# SCH_CH32V003EasyUSBBoard_SCH_2024-02-12.net
KiCad netlist of a schematic drawn in EasyEDA
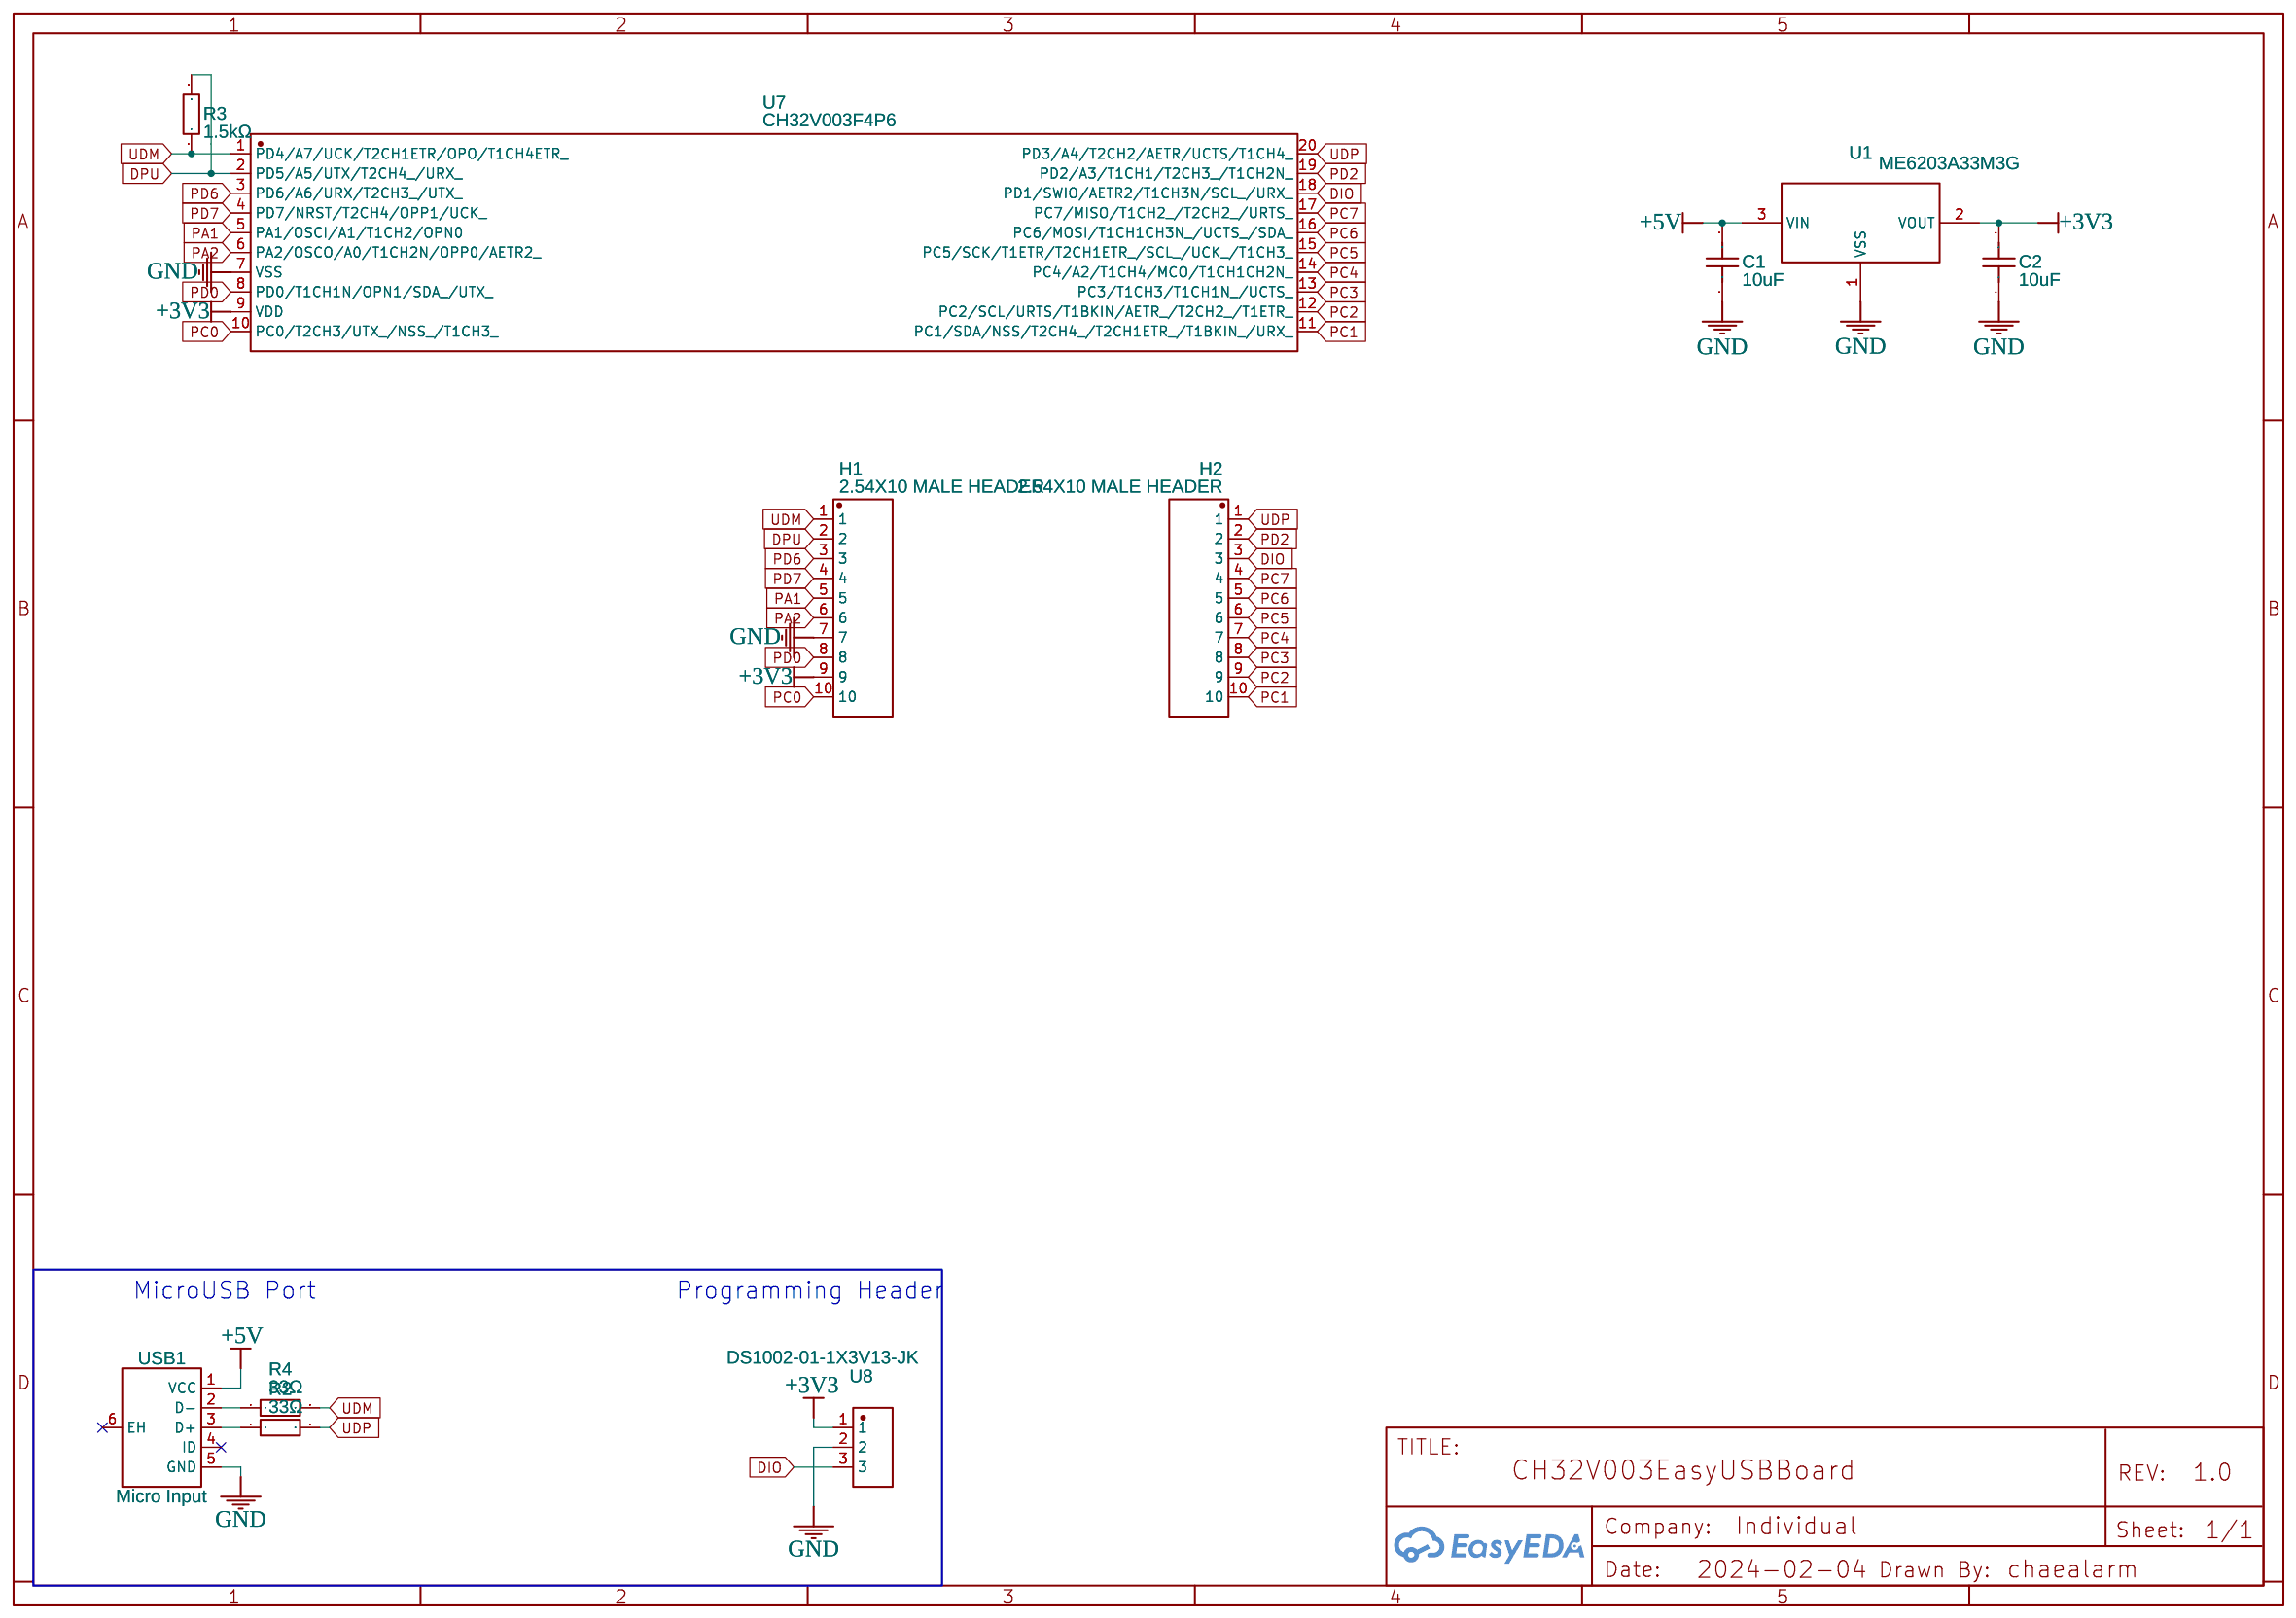
[diagram p0: schematic sheet]

(export (version "E")
  (design (tool "Eeschema 10.0.6"))
  (components
    (comp (ref "C1")
      (value "10uF")
      (fields
        (field (name "Manufacturer Part") "CL10A106KP8NNNC")
        (field (name "Manufacturer") "SAMSUNG(三星)")
      )
      (libsource (lib "") (part "CL10A106KP8NNNC"))
    )
    (comp (ref "C2")
      (value "10uF")
      (fields
        (field (name "Manufacturer Part") "CL10A106KP8NNNC")
        (field (name "Manufacturer") "SAMSUNG(三星)")
      )
      (libsource (lib "") (part "CL10A106KP8NNNC"))
    )
    (comp (ref "H1")
      (value "2.54X10 MALE HEADER")
      (fields
        (field (name "Manufacturer Part") "210S-1*11P L=11.6MMGold-plated black")
        (field (name "Manufacturer") "Ckmtw")
      )
      (libsource (lib "") (part "2.54X10 MALE HEADER"))
    )
    (comp (ref "H2")
      (value "2.54X10 MALE HEADER")
      (fields
        (field (name "Manufacturer Part") "210S-1*11P L=11.6MMGold-plated black")
        (field (name "Manufacturer") "Ckmtw")
      )
      (libsource (lib "") (part "2.54X10 MALE HEADER_1"))
    )
    (comp (ref "R2")
      (value "33Ω")
      (fields
        (field (name "Manufacturer Part") "0603WAF330JT5E")
        (field (name "Manufacturer") "UNI-ROYAL(厚声)")
      )
      (libsource (lib "") (part "0603WAF330JT5E"))
    )
    (comp (ref "R3")
      (value "1.5kΩ")
      (fields
        (field (name "Manufacturer Part") "0603WAF1501T5E")
        (field (name "Manufacturer") "UNI-ROYAL(厚声)")
      )
      (libsource (lib "") (part "0603WAF1501T5E"))
    )
    (comp (ref "R4")
      (value "33Ω")
      (fields
        (field (name "Manufacturer Part") "0603WAF330JT5E")
        (field (name "Manufacturer") "UNI-ROYAL(厚声)")
      )
      (libsource (lib "") (part "0603WAF330JT5E"))
    )
    (comp (ref "U1")
      (value "ME6203A33M3G")
      (fields (field (name "Manufacturer") "MICRONE(南京微盟)"))
      (libsource (lib "") (part "ME6203A33M3G"))
    )
    (comp (ref "U7") (value "CH32V003F4P6") (libsource (lib "") (part "CH32V003F4P6")))
    (comp (ref "U8")
      (value "DS1002-01-1X3V13-JK")
      (fields
        (field (name "Manufacturer Part") "DS1002-01-1x3V13-JK")
        (field (name "Manufacturer") "CONNFLY")
      )
      (libsource (lib "") (part "DS1002-01-1X3V13-JK"))
    )
    (comp (ref "USB1")
      (value "Micro Input")
      (fields
        (field (name "Manufacturer Part") "U254-051T-4BH23-S2B")
        (field (name "Manufacturer") "XKB Enterprise")
      )
      (libsource (lib "") (part "U254-051T-4BH23-S2B"))
    )
  )
  (nets
    (net (code "1") (name "+3V3") (class "Default")
      (node (ref "C2") (pin "2") (pinfunction "2_2") (pintype "unspecified"))
      (node (ref "H1") (pin "9") (pinfunction "9_9") (pintype "unspecified"))
      (node (ref "U1") (pin "2") (pinfunction "VOUT_2") (pintype "unspecified"))
      (node (ref "U7") (pin "9") (pinfunction "VDD_9") (pintype "unspecified"))
      (node (ref "U8") (pin "1") (pinfunction "1_1") (pintype "unspecified"))
    )
    (net (code "2") (name "+5V") (class "Default")
      (node (ref "C1") (pin "2") (pinfunction "2_2") (pintype "unspecified"))
      (node (ref "U1") (pin "3") (pinfunction "VIN_3") (pintype "unspecified"))
      (node (ref "USB1") (pin "1") (pinfunction "VCC_1") (pintype "input"))
    )
    (net (code "3") (name "DIO") (class "Default")
      (node (ref "H2") (pin "3") (pinfunction "3_3") (pintype "unspecified"))
      (node (ref "U7") (pin "18") (pinfunction "PD1/SWIO/AETR2/T1CH3N/SCL_/URX__18") (pintype "unspecified"))
      (node (ref "U8") (pin "3") (pinfunction "3_3") (pintype "unspecified"))
    )
    (net (code "4") (name "DPU") (class "Default")
      (node (ref "H1") (pin "2") (pinfunction "2_2") (pintype "unspecified"))
      (node (ref "R3") (pin "2") (pinfunction "2_2") (pintype "input"))
      (node (ref "U7") (pin "2") (pinfunction "PD5/A5/UTX/T2CH4_/URX__2") (pintype "unspecified"))
    )
    (net (code "5") (name "GND") (class "Default")
      (node (ref "C1") (pin "1") (pinfunction "1_1") (pintype "unspecified"))
      (node (ref "C2") (pin "1") (pinfunction "1_1") (pintype "unspecified"))
      (node (ref "H1") (pin "7") (pinfunction "7_7") (pintype "unspecified"))
      (node (ref "U1") (pin "1") (pinfunction "VSS_1") (pintype "unspecified"))
      (node (ref "U7") (pin "7") (pinfunction "VSS_7") (pintype "unspecified"))
      (node (ref "U8") (pin "2") (pinfunction "2_2") (pintype "unspecified"))
      (node (ref "USB1") (pin "5") (pinfunction "GND_5") (pintype "input"))
    )
    (net (code "6") (name "Net-(USB1-D+)") (class "Default")
      (node (ref "R2") (pin "1") (pinfunction "1_1") (pintype "input"))
      (node (ref "USB1") (pin "3") (pinfunction "D+_3") (pintype "input"))
    )
    (net (code "7") (name "Net-(USB1-D-)") (class "Default")
      (node (ref "R4") (pin "1") (pinfunction "1_1") (pintype "input"))
      (node (ref "USB1") (pin "2") (pinfunction "D-_2") (pintype "input"))
    )
    (net (code "8") (name "PA1") (class "Default")
      (node (ref "H1") (pin "5") (pinfunction "5_5") (pintype "unspecified"))
      (node (ref "U7") (pin "5") (pinfunction "PA1/OSCI/A1/T1CH2/OPN0_5") (pintype "unspecified"))
    )
    (net (code "9") (name "PA2") (class "Default")
      (node (ref "H1") (pin "6") (pinfunction "6_6") (pintype "unspecified"))
      (node (ref "U7") (pin "6") (pinfunction "PA2/OSCO/A0/T1CH2N/OPP0/AETR2__6") (pintype "unspecified"))
    )
    (net (code "10") (name "PC0") (class "Default")
      (node (ref "H1") (pin "10") (pinfunction "10_10") (pintype "unspecified"))
      (node (ref "U7") (pin "10") (pinfunction "PC0/T2CH3/UTX_/NSS_/T1CH3__10") (pintype "unspecified"))
    )
    (net (code "11") (name "PC1") (class "Default")
      (node (ref "H2") (pin "10") (pinfunction "10_10") (pintype "unspecified"))
      (node (ref "U7") (pin "11") (pinfunction "PC1/SDA/NSS/T2CH4_/T2CH1ETR_/T1BKIN_/URX__11") (pintype "unspecified"))
    )
    (net (code "12") (name "PC2") (class "Default")
      (node (ref "H2") (pin "9") (pinfunction "9_9") (pintype "unspecified"))
      (node (ref "U7") (pin "12") (pinfunction "PC2/SCL/URTS/T1BKIN/AETR_/T2CH2_/T1ETR__12") (pintype "unspecified"))
    )
    (net (code "13") (name "PC3") (class "Default")
      (node (ref "H2") (pin "8") (pinfunction "8_8") (pintype "unspecified"))
      (node (ref "U7") (pin "13") (pinfunction "PC3/T1CH3/T1CH1N_/UCTS__13") (pintype "unspecified"))
    )
    (net (code "14") (name "PC4") (class "Default")
      (node (ref "H2") (pin "7") (pinfunction "7_7") (pintype "unspecified"))
      (node (ref "U7") (pin "14") (pinfunction "PC4/A2/T1CH4/MCO/T1CH1CH2N__14") (pintype "unspecified"))
    )
    (net (code "15") (name "PC5") (class "Default")
      (node (ref "H2") (pin "6") (pinfunction "6_6") (pintype "unspecified"))
      (node (ref "U7") (pin "15") (pinfunction "PC5/SCK/T1ETR/T2CH1ETR_/SCL_/UCK_/T1CH3__15") (pintype "unspecified"))
    )
    (net (code "16") (name "PC6") (class "Default")
      (node (ref "H2") (pin "5") (pinfunction "5_5") (pintype "unspecified"))
      (node (ref "U7") (pin "16") (pinfunction "PC6/MOSI/T1CH1CH3N_/UCTS_/SDA__16") (pintype "unspecified"))
    )
    (net (code "17") (name "PC7") (class "Default")
      (node (ref "H2") (pin "4") (pinfunction "4_4") (pintype "unspecified"))
      (node (ref "U7") (pin "17") (pinfunction "PC7/MISO/T1CH2_/T2CH2_/URTS__17") (pintype "unspecified"))
    )
    (net (code "18") (name "PD0") (class "Default")
      (node (ref "H1") (pin "8") (pinfunction "8_8") (pintype "unspecified"))
      (node (ref "U7") (pin "8") (pinfunction "PD0/T1CH1N/OPN1/SDA_/UTX__8") (pintype "unspecified"))
    )
    (net (code "19") (name "PD2") (class "Default")
      (node (ref "H2") (pin "2") (pinfunction "2_2") (pintype "unspecified"))
      (node (ref "U7") (pin "19") (pinfunction "PD2/A3/T1CH1/T2CH3_/T1CH2N__19") (pintype "unspecified"))
    )
    (net (code "20") (name "PD6") (class "Default")
      (node (ref "H1") (pin "3") (pinfunction "3_3") (pintype "unspecified"))
      (node (ref "U7") (pin "3") (pinfunction "PD6/A6/URX/T2CH3_/UTX__3") (pintype "unspecified"))
    )
    (net (code "21") (name "PD7") (class "Default")
      (node (ref "H1") (pin "4") (pinfunction "4_4") (pintype "unspecified"))
      (node (ref "U7") (pin "4") (pinfunction "PD7/NRST/T2CH4/OPP1/UCK__4") (pintype "unspecified"))
    )
    (net (code "22") (name "UDM") (class "Default")
      (node (ref "H1") (pin "1") (pinfunction "1_1") (pintype "unspecified"))
      (node (ref "R3") (pin "1") (pinfunction "1_1") (pintype "input"))
      (node (ref "R4") (pin "2") (pinfunction "2_2") (pintype "input"))
      (node (ref "U7") (pin "1") (pinfunction "PD4/A7/UCK/T2CH1ETR/OPO/T1CH4ETR__1") (pintype "unspecified"))
    )
    (net (code "23") (name "UDP") (class "Default")
      (node (ref "H2") (pin "1") (pinfunction "1_1") (pintype "unspecified"))
      (node (ref "R2") (pin "2") (pinfunction "2_2") (pintype "input"))
      (node (ref "U7") (pin "20") (pinfunction "PD3/A4/T2CH2/AETR/UCTS/T1CH4__20") (pintype "unspecified"))
    )
    (net (code "24") (name "unconnected-(USB1-EH-Pad6)") (class "Default")
      (node (ref "USB1") (pin "6") (pinfunction "EH_6") (pintype "unspecified+no_connect"))
    )
    (net (code "25") (name "unconnected-(USB1-ID-Pad4)") (class "Default")
      (node (ref "USB1") (pin "4") (pinfunction "ID_4") (pintype "input+no_connect"))
    )
  )
)
